# UNO_Shield.net
KiCad netlist of a schematic drawn in EAGLE
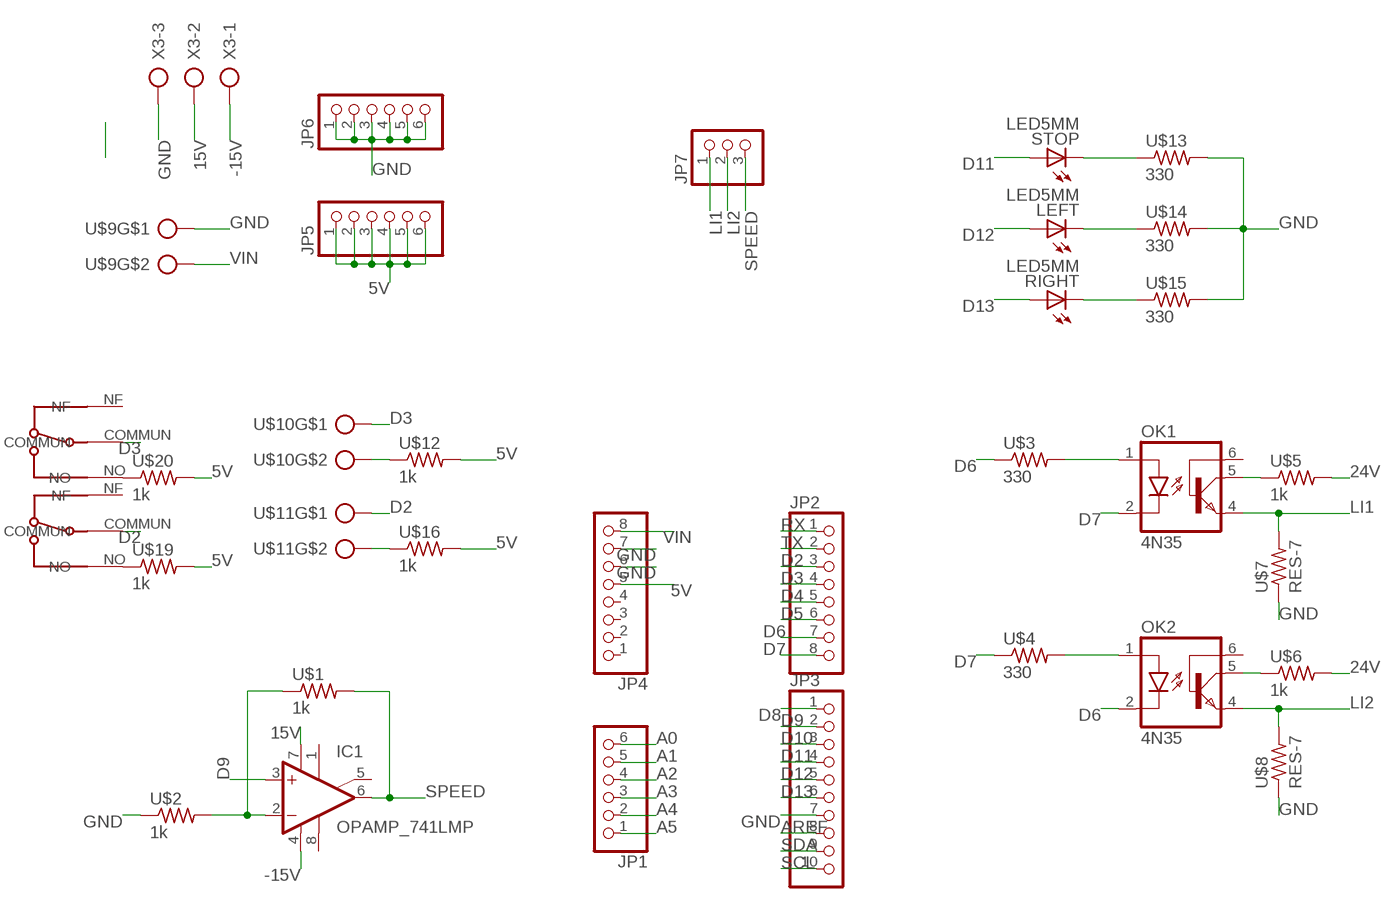
[diagram p0: schematic, sheet 1]

(export (version "E")
  (design (tool "Eeschema 10.0.6"))
  (components
    (comp (ref "IC1")
      (value "OPAMP_741LMP")
      (footprint "eagle-import:DIL08")
      (libsource (lib "eagle-import") (part "OPAMP_741PLM"))
    )
    (comp (ref "JP1")
      (value "PINHD-1X6")
      (footprint "eagle-import:1X06")
      (libsource (lib "eagle-import") (part "PINHD-1X6"))
    )
    (comp (ref "JP2")
      (value "PINHD-1X8")
      (footprint "eagle-import:1X08")
      (libsource (lib "eagle-import") (part "PINHD-1X8"))
    )
    (comp (ref "JP3")
      (value "PINHD-1X10")
      (footprint "eagle-import:1X10")
      (libsource (lib "eagle-import") (part "PINHD-1X10"))
    )
    (comp (ref "JP4")
      (value "PINHD-1X8")
      (footprint "eagle-import:1X08")
      (libsource (lib "eagle-import") (part "PINHD-1X8"))
    )
    (comp (ref "JP5")
      (value "PINHD-1X6")
      (footprint "eagle-import:1X06")
      (libsource (lib "eagle-import") (part "PINHD-1X6"))
    )
    (comp (ref "JP6")
      (value "PINHD-1X6")
      (footprint "eagle-import:1X06")
      (libsource (lib "eagle-import") (part "PINHD-1X6"))
    )
    (comp (ref "JP7")
      (value "PINHD-3_DATA")
      (footprint "eagle-import:1X03_DATA")
      (libsource (lib "eagle-import") (part "PINHD-3_DATA"))
    )
    (comp (ref "LEFT")
      (value "LED5MM")
      (footprint "eagle-import:LED5MM")
      (libsource (lib "eagle-import") (part "LED5MM"))
    )
    (comp (ref "OK1")
      (value "4N35")
      (footprint "eagle-import:DIL06")
      (fields (field (name "MF") "FAIRCHILD SEMICONDUCTOR"))
      (libsource (lib "eagle-import") (part "4N35"))
    )
    (comp (ref "OK2")
      (value "4N35")
      (footprint "eagle-import:DIL06")
      (fields (field (name "MF") "FAIRCHILD SEMICONDUCTOR"))
      (libsource (lib "eagle-import") (part "4N35"))
    )
    (comp (ref "RIGHT")
      (value "LED5MM")
      (footprint "eagle-import:LED5MM")
      (libsource (lib "eagle-import") (part "LED5MM"))
    )
    (comp (ref "STOP")
      (value "LED5MM")
      (footprint "eagle-import:LED5MM")
      (libsource (lib "eagle-import") (part "LED5MM"))
    )
    (comp (ref "U$1")
      (value "1k")
      (footprint "eagle-import:0204_7")
      (libsource (lib "eagle-import") (part "RES-7"))
    )
    (comp (ref "U$2")
      (value "1k")
      (footprint "eagle-import:0204_7")
      (libsource (lib "eagle-import") (part "RES-7"))
    )
    (comp (ref "U$3")
      (value "330")
      (footprint "eagle-import:0204_7")
      (libsource (lib "eagle-import") (part "RES-7"))
    )
    (comp (ref "U$4")
      (value "330")
      (footprint "eagle-import:0204_7")
      (libsource (lib "eagle-import") (part "RES-7"))
    )
    (comp (ref "U$5")
      (value "1k")
      (footprint "eagle-import:0204_7")
      (libsource (lib "eagle-import") (part "RES-7"))
    )
    (comp (ref "U$6")
      (value "1k")
      (footprint "eagle-import:0204_7")
      (libsource (lib "eagle-import") (part "RES-7"))
    )
    (comp (ref "U$7")
      (value "RES-7")
      (footprint "eagle-import:0204_7")
      (libsource (lib "eagle-import") (part "RES-7"))
    )
    (comp (ref "U$8")
      (value "RES-7")
      (footprint "eagle-import:0204_7")
      (libsource (lib "eagle-import") (part "RES-7"))
    )
    (comp (ref "U$9")
      (value "CON_PTR_2")
      (footprint "eagle-import:AK300_2")
      (libsource (lib "eagle-import") (part "CON_PTR_2"))
    )
    (comp (ref "U$10")
      (value "CON_PTR_2")
      (footprint "eagle-import:AK300_2")
      (libsource (lib "eagle-import") (part "CON_PTR_2"))
    )
    (comp (ref "U$11")
      (value "CON_PTR_2")
      (footprint "eagle-import:AK300_2")
      (libsource (lib "eagle-import") (part "CON_PTR_2"))
    )
    (comp (ref "U$12")
      (value "1k")
      (footprint "eagle-import:0204_7")
      (libsource (lib "eagle-import") (part "RES-7"))
    )
    (comp (ref "U$13")
      (value "330")
      (footprint "eagle-import:0204_7")
      (libsource (lib "eagle-import") (part "RES-7"))
    )
    (comp (ref "U$14")
      (value "330")
      (footprint "eagle-import:0204_7")
      (libsource (lib "eagle-import") (part "RES-7"))
    )
    (comp (ref "U$15")
      (value "330")
      (footprint "eagle-import:0204_7")
      (libsource (lib "eagle-import") (part "RES-7"))
    )
    (comp (ref "U$16")
      (value "1k")
      (footprint "eagle-import:0204_7")
      (libsource (lib "eagle-import") (part "RES-7"))
    )
    (comp (ref "U$17")
      (value "MICROSWITCHCOUDE")
      (footprint "eagle-import:DG23-B3RA")
      (libsource (lib "eagle-import") (part "MICROSWITCHCOUDE"))
    )
    (comp (ref "U$18")
      (value "MICROSWITCHCOUDE")
      (footprint "eagle-import:DG23-B3RA")
      (libsource (lib "eagle-import") (part "MICROSWITCHCOUDE"))
    )
    (comp (ref "U$19")
      (value "1k")
      (footprint "eagle-import:0204_7")
      (libsource (lib "eagle-import") (part "RES-7"))
    )
    (comp (ref "U$20")
      (value "1k")
      (footprint "eagle-import:0204_7")
      (libsource (lib "eagle-import") (part "RES-7"))
    )
    (comp (ref "X3")
      (value "CON_PTR_3")
      (footprint "eagle-import:AK300_3")
      (libsource (lib "eagle-import") (part "CON_PTR_3"))
    )
  )
  (nets
    (net (code "1") (name "/-15V") (class "Default")
      (node (ref "IC1") (pin "4") (pinfunction "V-_4") (pintype "power_in"))
      (node (ref "X3") (pin "1") (pinfunction "KL_1") (pintype "passive"))
    )
    (net (code "2") (name "/5V") (class "Default")
      (node (ref "JP4") (pin "5") (pinfunction "5_5") (pintype "passive"))
      (node (ref "JP5") (pin "1") (pinfunction "1_1") (pintype "passive"))
      (node (ref "JP5") (pin "2") (pinfunction "2_2") (pintype "passive"))
      (node (ref "JP5") (pin "3") (pinfunction "3_3") (pintype "passive"))
      (node (ref "JP5") (pin "4") (pinfunction "4_4") (pintype "passive"))
      (node (ref "JP5") (pin "5") (pinfunction "5_5") (pintype "passive"))
      (node (ref "JP5") (pin "6") (pinfunction "6_6") (pintype "passive"))
      (node (ref "U$12") (pin "2") (pinfunction "2_2") (pintype "passive"))
      (node (ref "U$16") (pin "2") (pinfunction "2_2") (pintype "passive"))
      (node (ref "U$19") (pin "2") (pinfunction "2_2") (pintype "passive"))
      (node (ref "U$20") (pin "2") (pinfunction "2_2") (pintype "passive"))
    )
    (net (code "3") (name "/15V") (class "Default")
      (node (ref "IC1") (pin "7") (pinfunction "V+_7") (pintype "power_in"))
      (node (ref "X3") (pin "2") (pinfunction "KL_2") (pintype "passive"))
    )
    (net (code "4") (name "/24V") (class "Default")
      (node (ref "U$5") (pin "2") (pinfunction "2_2") (pintype "passive"))
      (node (ref "U$6") (pin "2") (pinfunction "2_2") (pintype "passive"))
    )
    (net (code "5") (name "/A0") (class "Default")
      (node (ref "JP1") (pin "6") (pinfunction "6_6") (pintype "passive"))
    )
    (net (code "6") (name "/A1") (class "Default")
      (node (ref "JP1") (pin "5") (pinfunction "5_5") (pintype "passive"))
    )
    (net (code "7") (name "/A2") (class "Default")
      (node (ref "JP1") (pin "4") (pinfunction "4_4") (pintype "passive"))
    )
    (net (code "8") (name "/A3") (class "Default")
      (node (ref "JP1") (pin "3") (pinfunction "3_3") (pintype "passive"))
    )
    (net (code "9") (name "/A4") (class "Default")
      (node (ref "JP1") (pin "2") (pinfunction "2_2") (pintype "passive"))
    )
    (net (code "10") (name "/A5") (class "Default")
      (node (ref "JP1") (pin "1") (pinfunction "1_1") (pintype "passive"))
    )
    (net (code "11") (name "/AREF") (class "Default")
      (node (ref "JP3") (pin "8") (pinfunction "8_8") (pintype "passive"))
    )
    (net (code "12") (name "/D2") (class "Default")
      (node (ref "JP2") (pin "3") (pinfunction "3_3") (pintype "passive"))
      (node (ref "U$11") (pin "1") (pinfunction "KL_1") (pintype "passive"))
      (node (ref "U$18") (pin "COMMUN") (pinfunction "COMMUN_COMMUN") (pintype "bidirectional"))
    )
    (net (code "13") (name "/D3") (class "Default")
      (node (ref "JP2") (pin "4") (pinfunction "4_4") (pintype "passive"))
      (node (ref "U$10") (pin "1") (pinfunction "KL_1") (pintype "passive"))
      (node (ref "U$17") (pin "COMMUN") (pinfunction "COMMUN_COMMUN") (pintype "bidirectional"))
    )
    (net (code "14") (name "/D4") (class "Default")
      (node (ref "JP2") (pin "5") (pinfunction "5_5") (pintype "passive"))
    )
    (net (code "15") (name "/D5") (class "Default")
      (node (ref "JP2") (pin "6") (pinfunction "6_6") (pintype "passive"))
    )
    (net (code "16") (name "/D6") (class "Default")
      (node (ref "JP2") (pin "7") (pinfunction "7_7") (pintype "passive"))
      (node (ref "OK1") (pin "1") (pinfunction "A_1") (pintype "passive"))
      (node (ref "OK2") (pin "2") (pinfunction "C_2") (pintype "passive"))
      (node (ref "U$3") (pin "1") (pinfunction "1_1") (pintype "passive"))
      (node (ref "U$3") (pin "2") (pinfunction "2_2") (pintype "passive"))
    )
    (net (code "17") (name "/D7") (class "Default")
      (node (ref "JP2") (pin "8") (pinfunction "8_8") (pintype "passive"))
      (node (ref "OK1") (pin "2") (pinfunction "C_2") (pintype "passive"))
      (node (ref "OK2") (pin "1") (pinfunction "A_1") (pintype "passive"))
      (node (ref "U$4") (pin "1") (pinfunction "1_1") (pintype "passive"))
      (node (ref "U$4") (pin "2") (pinfunction "2_2") (pintype "passive"))
    )
    (net (code "18") (name "/D8") (class "Default")
      (node (ref "JP3") (pin "1") (pinfunction "1_1") (pintype "passive"))
    )
    (net (code "19") (name "/D9") (class "Default")
      (node (ref "IC1") (pin "3") (pinfunction "+IN_3") (pintype "input"))
      (node (ref "JP3") (pin "2") (pinfunction "2_2") (pintype "passive"))
    )
    (net (code "20") (name "/D10") (class "Default")
      (node (ref "JP3") (pin "3") (pinfunction "3_3") (pintype "passive"))
    )
    (net (code "21") (name "/D11") (class "Default")
      (node (ref "JP3") (pin "4") (pinfunction "4_4") (pintype "passive"))
      (node (ref "STOP") (pin "A") (pinfunction "A_A") (pintype "passive"))
    )
    (net (code "22") (name "/D12") (class "Default")
      (node (ref "JP3") (pin "5") (pinfunction "5_5") (pintype "passive"))
      (node (ref "LEFT") (pin "A") (pinfunction "A_A") (pintype "passive"))
    )
    (net (code "23") (name "/D13") (class "Default")
      (node (ref "JP3") (pin "6") (pinfunction "6_6") (pintype "passive"))
      (node (ref "RIGHT") (pin "A") (pinfunction "A_A") (pintype "passive"))
    )
    (net (code "24") (name "/GND") (class "Default")
      (node (ref "JP3") (pin "7") (pinfunction "7_7") (pintype "passive"))
      (node (ref "JP4") (pin "6") (pinfunction "6_6") (pintype "passive"))
      (node (ref "JP4") (pin "7") (pinfunction "7_7") (pintype "passive"))
      (node (ref "JP6") (pin "1") (pinfunction "1_1") (pintype "passive"))
      (node (ref "JP6") (pin "2") (pinfunction "2_2") (pintype "passive"))
      (node (ref "JP6") (pin "3") (pinfunction "3_3") (pintype "passive"))
      (node (ref "JP6") (pin "4") (pinfunction "4_4") (pintype "passive"))
      (node (ref "JP6") (pin "5") (pinfunction "5_5") (pintype "passive"))
      (node (ref "JP6") (pin "6") (pinfunction "6_6") (pintype "passive"))
      (node (ref "U$13") (pin "2") (pinfunction "2_2") (pintype "passive"))
      (node (ref "U$14") (pin "2") (pinfunction "2_2") (pintype "passive"))
      (node (ref "U$15") (pin "2") (pinfunction "2_2") (pintype "passive"))
      (node (ref "U$2") (pin "1") (pinfunction "1_1") (pintype "passive"))
      (node (ref "U$7") (pin "1") (pinfunction "1_1") (pintype "passive"))
      (node (ref "U$8") (pin "1") (pinfunction "1_1") (pintype "passive"))
      (node (ref "U$9") (pin "1") (pinfunction "KL_1") (pintype "passive"))
      (node (ref "X3") (pin "3") (pinfunction "KL_3") (pintype "passive"))
    )
    (net (code "25") (name "/LI1") (class "Default")
      (node (ref "JP7") (pin "1") (pinfunction "1_1") (pintype "passive"))
      (node (ref "OK1") (pin "4") (pinfunction "EMI_4") (pintype "passive"))
      (node (ref "U$7") (pin "2") (pinfunction "2_2") (pintype "passive"))
    )
    (net (code "26") (name "/LI2") (class "Default")
      (node (ref "JP7") (pin "2") (pinfunction "2_2") (pintype "passive"))
      (node (ref "OK2") (pin "4") (pinfunction "EMI_4") (pintype "passive"))
      (node (ref "U$8") (pin "2") (pinfunction "2_2") (pintype "passive"))
    )
    (net (code "27") (name "/RX") (class "Default")
      (node (ref "JP2") (pin "1") (pinfunction "1_1") (pintype "passive"))
    )
    (net (code "28") (name "/SCL") (class "Default")
      (node (ref "JP3") (pin "10") (pinfunction "10_10") (pintype "passive"))
    )
    (net (code "29") (name "/SDA") (class "Default")
      (node (ref "JP3") (pin "9") (pinfunction "9_9") (pintype "passive"))
    )
    (net (code "30") (name "/SPEED") (class "Default")
      (node (ref "IC1") (pin "6") (pinfunction "OUT_6") (pintype "output"))
      (node (ref "JP7") (pin "3") (pinfunction "3_3") (pintype "passive"))
      (node (ref "U$1") (pin "2") (pinfunction "2_2") (pintype "passive"))
    )
    (net (code "31") (name "/TX") (class "Default")
      (node (ref "JP2") (pin "2") (pinfunction "2_2") (pintype "passive"))
    )
    (net (code "32") (name "/VIN") (class "Default")
      (node (ref "JP4") (pin "8") (pinfunction "8_8") (pintype "passive"))
      (node (ref "U$9") (pin "2") (pinfunction "KL_2") (pintype "passive"))
    )
    (net (code "33") (name "Net-(IC1--IN)") (class "Default")
      (node (ref "IC1") (pin "2") (pinfunction "-IN_2") (pintype "input"))
      (node (ref "U$1") (pin "1") (pinfunction "1_1") (pintype "passive"))
      (node (ref "U$2") (pin "2") (pinfunction "2_2") (pintype "passive"))
    )
    (net (code "34") (name "Net-(LEFT-C)") (class "Default")
      (node (ref "LEFT") (pin "K") (pinfunction "C_K") (pintype "passive"))
      (node (ref "U$14") (pin "1") (pinfunction "1_1") (pintype "passive"))
    )
    (net (code "35") (name "Net-(OK1-COL)") (class "Default")
      (node (ref "OK1") (pin "5") (pinfunction "COL_5") (pintype "passive"))
      (node (ref "U$5") (pin "1") (pinfunction "1_1") (pintype "passive"))
    )
    (net (code "36") (name "Net-(OK2-COL)") (class "Default")
      (node (ref "OK2") (pin "5") (pinfunction "COL_5") (pintype "passive"))
      (node (ref "U$6") (pin "1") (pinfunction "1_1") (pintype "passive"))
    )
    (net (code "37") (name "Net-(RIGHT-C)") (class "Default")
      (node (ref "RIGHT") (pin "K") (pinfunction "C_K") (pintype "passive"))
      (node (ref "U$15") (pin "1") (pinfunction "1_1") (pintype "passive"))
    )
    (net (code "38") (name "Net-(STOP-C)") (class "Default")
      (node (ref "STOP") (pin "K") (pinfunction "C_K") (pintype "passive"))
      (node (ref "U$13") (pin "1") (pinfunction "1_1") (pintype "passive"))
    )
    (net (code "39") (name "Net-(U$10B-KL)") (class "Default")
      (node (ref "U$10") (pin "2") (pinfunction "KL_2") (pintype "passive"))
      (node (ref "U$12") (pin "1") (pinfunction "1_1") (pintype "passive"))
    )
    (net (code "40") (name "Net-(U$11B-KL)") (class "Default")
      (node (ref "U$11") (pin "2") (pinfunction "KL_2") (pintype "passive"))
      (node (ref "U$16") (pin "1") (pinfunction "1_1") (pintype "passive"))
    )
    (net (code "41") (name "Net-(U$17-PadNO)") (class "Default")
      (node (ref "U$17") (pin "NO") (pinfunction "NO_NO") (pintype "bidirectional"))
      (node (ref "U$20") (pin "1") (pinfunction "1_1") (pintype "passive"))
    )
    (net (code "42") (name "Net-(U$18-PadNO)") (class "Default")
      (node (ref "U$18") (pin "NO") (pinfunction "NO_NO") (pintype "bidirectional"))
      (node (ref "U$19") (pin "1") (pinfunction "1_1") (pintype "passive"))
    )
    (net (code "43") (name "unconnected-(IC1-ON1-Pad1)") (class "Default")
      (node (ref "IC1") (pin "1") (pinfunction "ON1_1") (pintype "passive"))
    )
    (net (code "44") (name "unconnected-(IC1-ON2-Pad5)") (class "Default")
      (node (ref "IC1") (pin "5") (pinfunction "ON2_5") (pintype "passive"))
    )
    (net (code "45") (name "unconnected-(IC1-OPT-Pad8)") (class "Default")
      (node (ref "IC1") (pin "8") (pinfunction "OPT_8") (pintype "passive"))
    )
    (net (code "46") (name "unconnected-(JP4-Pad1)") (class "Default")
      (node (ref "JP4") (pin "1") (pinfunction "1_1") (pintype "passive"))
    )
    (net (code "47") (name "unconnected-(JP4-Pad2)") (class "Default")
      (node (ref "JP4") (pin "2") (pinfunction "2_2") (pintype "passive"))
    )
    (net (code "48") (name "unconnected-(JP4-Pad3)") (class "Default")
      (node (ref "JP4") (pin "3") (pinfunction "3_3") (pintype "passive"))
    )
    (net (code "49") (name "unconnected-(JP4-Pad4)") (class "Default")
      (node (ref "JP4") (pin "4") (pinfunction "4_4") (pintype "passive"))
    )
    (net (code "50") (name "unconnected-(OK1-BAS-Pad6)") (class "Default")
      (node (ref "OK1") (pin "6") (pinfunction "BAS_6") (pintype "passive"))
    )
    (net (code "51") (name "unconnected-(OK2-BAS-Pad6)") (class "Default")
      (node (ref "OK2") (pin "6") (pinfunction "BAS_6") (pintype "passive"))
    )
    (net (code "52") (name "unconnected-(U$17-PadNF)") (class "Default")
      (node (ref "U$17") (pin "NF") (pinfunction "NF_NF") (pintype "bidirectional"))
    )
    (net (code "53") (name "unconnected-(U$18-PadNF)") (class "Default")
      (node (ref "U$18") (pin "NF") (pinfunction "NF_NF") (pintype "bidirectional"))
    )
  )
)
